# Ports.net
KiCad netlist of a schematic drawn in Altium Designer
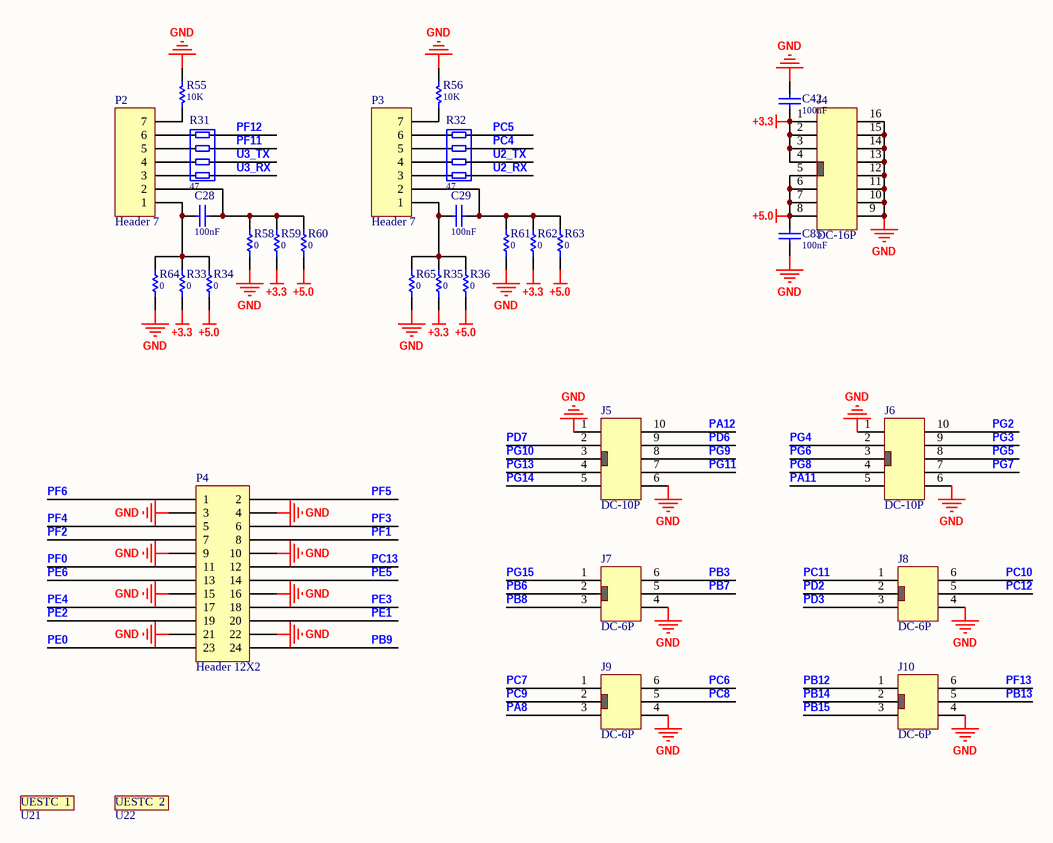
[diagram p0: Ports.SchDoc]

(export (version "E")
  (design (tool "Eeschema 10.0.6"))
  (components
    (comp (ref "C28")
      (value "100nF")
      (footprint "C0603-L")
      (description "贴片瓷片电容")
      (fields (field (name "Comment") "Cap-S"))
      (libsource (lib "xz_D") (part "Cap-S"))
    )
    (comp (ref "C29")
      (value "100nF")
      (footprint "C0603-L")
      (description "贴片瓷片电容")
      (fields (field (name "Comment") "Cap-S"))
      (libsource (lib "xz_D") (part "Cap-S"))
    )
    (comp (ref "C42")
      (value "100nF")
      (footprint "C0603-L")
      (description "贴片瓷片电容")
      (fields (field (name "Comment") "Cap-S"))
      (libsource (lib "xz_D") (part "Cap-S"))
    )
    (comp (ref "C85")
      (value "100nF")
      (footprint "C0603-L")
      (description "贴片瓷片电容")
      (fields (field (name "Comment") "Cap-S"))
      (libsource (lib "xz_D") (part "Cap-S"))
    )
    (comp (ref "J4") (value "DC-16P") (footprint "DC-16P") (libsource (lib "CommonUsed") (part "DC-16P")))
    (comp (ref "J5") (value "DC-10P") (footprint "DC-10P") (libsource (lib "CommonUsed") (part "DC-10P")))
    (comp (ref "J6") (value "DC-10P") (footprint "DC-10P") (libsource (lib "CommonUsed") (part "DC-10P")))
    (comp (ref "J7") (value "DC-6P") (footprint "DC-6P") (libsource (lib "CommonUsed") (part "DC-6P")))
    (comp (ref "J8") (value "DC-6P") (footprint "DC-6P") (libsource (lib "CommonUsed") (part "DC-6P")))
    (comp (ref "J9") (value "DC-6P") (footprint "DC-6P") (libsource (lib "CommonUsed") (part "DC-6P")))
    (comp (ref "J10") (value "DC-6P") (footprint "DC-6P") (libsource (lib "CommonUsed") (part "DC-6P")))
    (comp (ref "P2")
      (value "Header 7")
      (footprint "HDR1X7")
      (description "Header, 7-Pin")
      (fields (field (name "PUBLISHER") "Altium Limited"))
      (libsource (lib "xz_C") (part "Header 7"))
    )
    (comp (ref "P3")
      (value "Header 7")
      (footprint "HDR1X7")
      (description "Header, 7-Pin")
      (fields (field (name "PUBLISHER") "Altium Limited"))
      (libsource (lib "xz_C") (part "Header 7"))
    )
    (comp (ref "P4")
      (value "Header 12X2")
      (footprint "HDR2X12")
      (description "Header, 12-Pin, Dual row")
      (fields (field (name "PUBLISHER") "Altium Limited"))
      (libsource (lib "xz_C") (part "Header 12X2"))
    )
    (comp (ref "R31")
      (value "47")
      (footprint "R0603X4")
      (description "排阻 4")
      (fields (field (name "Comment") "R"))
      (libsource (lib "xz_D") (part "Res-4R"))
    )
    (comp (ref "R32")
      (value "47")
      (footprint "R0603X4")
      (description "排阻 4")
      (fields (field (name "Comment") "R"))
      (libsource (lib "xz_D") (part "Res-4R"))
    )
    (comp (ref "R33")
      (value "0")
      (footprint "R0603-L")
      (description "贴片电阻")
      (fields (field (name "Comment") "R"))
      (libsource (lib "xz_D") (part "Res"))
    )
    (comp (ref "R34")
      (value "0")
      (footprint "R0603-L")
      (description "贴片电阻")
      (fields (field (name "Comment") "R"))
      (libsource (lib "xz_D") (part "Res"))
    )
    (comp (ref "R35")
      (value "0")
      (footprint "R0603-L")
      (description "贴片电阻")
      (fields (field (name "Comment") "R"))
      (libsource (lib "xz_D") (part "Res"))
    )
    (comp (ref "R36")
      (value "0")
      (footprint "R0603-L")
      (description "贴片电阻")
      (fields (field (name "Comment") "R"))
      (libsource (lib "xz_D") (part "Res"))
    )
    (comp (ref "R55")
      (value "10K")
      (footprint "R0603-L")
      (description "贴片电阻")
      (fields (field (name "Comment") "R"))
      (libsource (lib "xz_D") (part "Res"))
    )
    (comp (ref "R56")
      (value "10K")
      (footprint "R0603-L")
      (description "贴片电阻")
      (fields (field (name "Comment") "R"))
      (libsource (lib "xz_D") (part "Res"))
    )
    (comp (ref "R58")
      (value "0")
      (footprint "R0603-L")
      (description "贴片电阻")
      (fields (field (name "Comment") "R"))
      (libsource (lib "xz_D") (part "Res"))
    )
    (comp (ref "R59")
      (value "0")
      (footprint "R0603-L")
      (description "贴片电阻")
      (fields (field (name "Comment") "R"))
      (libsource (lib "xz_D") (part "Res"))
    )
    (comp (ref "R60")
      (value "0")
      (footprint "R0603-L")
      (description "贴片电阻")
      (fields (field (name "Comment") "R"))
      (libsource (lib "xz_D") (part "Res"))
    )
    (comp (ref "R61")
      (value "0")
      (footprint "R0603-L")
      (description "贴片电阻")
      (fields (field (name "Comment") "R"))
      (libsource (lib "xz_D") (part "Res"))
    )
    (comp (ref "R62")
      (value "0")
      (footprint "R0603-L")
      (description "贴片电阻")
      (fields (field (name "Comment") "R"))
      (libsource (lib "xz_D") (part "Res"))
    )
    (comp (ref "R63")
      (value "0")
      (footprint "R0603-L")
      (description "贴片电阻")
      (fields (field (name "Comment") "R"))
      (libsource (lib "xz_D") (part "Res"))
    )
    (comp (ref "R64")
      (value "0")
      (footprint "R0603-L")
      (description "贴片电阻")
      (fields (field (name "Comment") "R"))
      (libsource (lib "xz_D") (part "Res"))
    )
    (comp (ref "R65")
      (value "0")
      (footprint "R0603-L")
      (description "贴片电阻")
      (fields (field (name "Comment") "R"))
      (libsource (lib "xz_D") (part "Res"))
    )
    (comp (ref "U21") (value "UESTC  1") (footprint "UESTC") (libsource (lib "CommonUsed") (part "UESTC  1")))
    (comp (ref "U22")
      (value "UESTC  2")
      (footprint "UESTC  2")
      (libsource (lib "CommonUsed") (part "UESTC  2"))
    )
  )
  (nets
    (net (code "1") (name "+3.3") (class "Default")
      (node (ref "C42") (pin "2") (pinfunction "2_2") (pintype "passive"))
      (node (ref "J4") (pin "1") (pinfunction "1_1") (pintype "passive"))
      (node (ref "J4") (pin "2") (pinfunction "2_2") (pintype "passive"))
      (node (ref "J4") (pin "3") (pinfunction "3_3") (pintype "passive"))
      (node (ref "J4") (pin "4") (pinfunction "4_4") (pintype "passive"))
      (node (ref "R33") (pin "1") (pinfunction "1_1") (pintype "passive"))
      (node (ref "R35") (pin "1") (pinfunction "1_1") (pintype "passive"))
      (node (ref "R59") (pin "1") (pinfunction "1_1") (pintype "passive"))
      (node (ref "R62") (pin "1") (pinfunction "1_1") (pintype "passive"))
    )
    (net (code "2") (name "+5.0") (class "Default")
      (node (ref "C85") (pin "1") (pinfunction "1_1") (pintype "passive"))
      (node (ref "J4") (pin "5") (pinfunction "5_5") (pintype "passive"))
      (node (ref "J4") (pin "6") (pinfunction "6_6") (pintype "passive"))
      (node (ref "J4") (pin "7") (pinfunction "7_7") (pintype "passive"))
      (node (ref "J4") (pin "8") (pinfunction "8_8") (pintype "passive"))
      (node (ref "R34") (pin "1") (pinfunction "1_1") (pintype "passive"))
      (node (ref "R36") (pin "1") (pinfunction "1_1") (pintype "passive"))
      (node (ref "R60") (pin "1") (pinfunction "1_1") (pintype "passive"))
      (node (ref "R63") (pin "1") (pinfunction "1_1") (pintype "passive"))
    )
    (net (code "3") (name "/PA8") (class "Default")
      (node (ref "J9") (pin "3") (pinfunction "3_3") (pintype "passive"))
    )
    (net (code "4") (name "/PA11") (class "Default")
      (node (ref "J6") (pin "5") (pinfunction "5_5") (pintype "passive"))
    )
    (net (code "5") (name "/PA12") (class "Default")
      (node (ref "J5") (pin "10") (pinfunction "10_10") (pintype "passive"))
    )
    (net (code "6") (name "/PB3") (class "Default")
      (node (ref "J7") (pin "6") (pinfunction "6_6") (pintype "passive"))
    )
    (net (code "7") (name "/PB6") (class "Default")
      (node (ref "J7") (pin "2") (pinfunction "2_2") (pintype "passive"))
    )
    (net (code "8") (name "/PB7") (class "Default")
      (node (ref "J7") (pin "5") (pinfunction "5_5") (pintype "passive"))
    )
    (net (code "9") (name "/PB8") (class "Default")
      (node (ref "J7") (pin "3") (pinfunction "3_3") (pintype "passive"))
    )
    (net (code "10") (name "/PB9") (class "Default")
      (node (ref "P4") (pin "24") (pinfunction "24_24") (pintype "passive"))
    )
    (net (code "11") (name "/PB12") (class "Default")
      (node (ref "J10") (pin "1") (pinfunction "1_1") (pintype "passive"))
    )
    (net (code "12") (name "/PB13") (class "Default")
      (node (ref "J10") (pin "5") (pinfunction "5_5") (pintype "passive"))
    )
    (net (code "13") (name "/PB14") (class "Default")
      (node (ref "J10") (pin "2") (pinfunction "2_2") (pintype "passive"))
    )
    (net (code "14") (name "/PB15") (class "Default")
      (node (ref "J10") (pin "3") (pinfunction "3_3") (pintype "passive"))
    )
    (net (code "15") (name "/PC4") (class "Default") (node (ref "R32") (pin "3") (pintype "passive")))
    (net (code "16") (name "/PC5") (class "Default") (node (ref "R32") (pin "4") (pintype "passive")))
    (net (code "17") (name "/PC6") (class "Default")
      (node (ref "J9") (pin "6") (pinfunction "6_6") (pintype "passive"))
    )
    (net (code "18") (name "/PC7") (class "Default")
      (node (ref "J9") (pin "1") (pinfunction "1_1") (pintype "passive"))
    )
    (net (code "19") (name "/PC8") (class "Default")
      (node (ref "J9") (pin "5") (pinfunction "5_5") (pintype "passive"))
    )
    (net (code "20") (name "/PC9") (class "Default")
      (node (ref "J9") (pin "2") (pinfunction "2_2") (pintype "passive"))
    )
    (net (code "21") (name "/PC10") (class "Default")
      (node (ref "J8") (pin "6") (pinfunction "6_6") (pintype "passive"))
    )
    (net (code "22") (name "/PC11") (class "Default")
      (node (ref "J8") (pin "1") (pinfunction "1_1") (pintype "passive"))
    )
    (net (code "23") (name "/PC12") (class "Default")
      (node (ref "J8") (pin "5") (pinfunction "5_5") (pintype "passive"))
    )
    (net (code "24") (name "/PC13") (class "Default")
      (node (ref "P4") (pin "12") (pinfunction "12_12") (pintype "passive"))
    )
    (net (code "25") (name "/PD2") (class "Default")
      (node (ref "J8") (pin "2") (pinfunction "2_2") (pintype "passive"))
    )
    (net (code "26") (name "/PD3") (class "Default")
      (node (ref "J8") (pin "3") (pinfunction "3_3") (pintype "passive"))
    )
    (net (code "27") (name "/PD6") (class "Default")
      (node (ref "J5") (pin "9") (pinfunction "9_9") (pintype "passive"))
    )
    (net (code "28") (name "/PD7") (class "Default")
      (node (ref "J5") (pin "2") (pinfunction "2_2") (pintype "passive"))
    )
    (net (code "29") (name "/PE0") (class "Default")
      (node (ref "P4") (pin "23") (pinfunction "23_23") (pintype "passive"))
    )
    (net (code "30") (name "/PE1") (class "Default")
      (node (ref "P4") (pin "20") (pinfunction "20_20") (pintype "passive"))
    )
    (net (code "31") (name "/PE2") (class "Default")
      (node (ref "P4") (pin "19") (pinfunction "19_19") (pintype "passive"))
    )
    (net (code "32") (name "/PE3") (class "Default")
      (node (ref "P4") (pin "18") (pinfunction "18_18") (pintype "passive"))
    )
    (net (code "33") (name "/PE4") (class "Default")
      (node (ref "P4") (pin "17") (pinfunction "17_17") (pintype "passive"))
    )
    (net (code "34") (name "/PE5") (class "Default")
      (node (ref "P4") (pin "14") (pinfunction "14_14") (pintype "passive"))
    )
    (net (code "35") (name "/PE6") (class "Default")
      (node (ref "P4") (pin "13") (pinfunction "13_13") (pintype "passive"))
    )
    (net (code "36") (name "/PF0") (class "Default")
      (node (ref "P4") (pin "11") (pinfunction "11_11") (pintype "passive"))
    )
    (net (code "37") (name "/PF1") (class "Default")
      (node (ref "P4") (pin "8") (pinfunction "8_8") (pintype "passive"))
    )
    (net (code "38") (name "/PF2") (class "Default")
      (node (ref "P4") (pin "7") (pinfunction "7_7") (pintype "passive"))
    )
    (net (code "39") (name "/PF3") (class "Default")
      (node (ref "P4") (pin "6") (pinfunction "6_6") (pintype "passive"))
    )
    (net (code "40") (name "/PF4") (class "Default")
      (node (ref "P4") (pin "5") (pinfunction "5_5") (pintype "passive"))
    )
    (net (code "41") (name "/PF5") (class "Default")
      (node (ref "P4") (pin "2") (pinfunction "2_2") (pintype "passive"))
    )
    (net (code "42") (name "/PF6") (class "Default")
      (node (ref "P4") (pin "1") (pinfunction "1_1") (pintype "passive"))
    )
    (net (code "43") (name "/PF11") (class "Default") (node (ref "R31") (pin "3") (pintype "passive")))
    (net (code "44") (name "/PF12") (class "Default") (node (ref "R31") (pin "4") (pintype "passive")))
    (net (code "45") (name "/PF13") (class "Default")
      (node (ref "J10") (pin "6") (pinfunction "6_6") (pintype "passive"))
    )
    (net (code "46") (name "/PG2") (class "Default")
      (node (ref "J6") (pin "10") (pinfunction "10_10") (pintype "passive"))
    )
    (net (code "47") (name "/PG3") (class "Default")
      (node (ref "J6") (pin "9") (pinfunction "9_9") (pintype "passive"))
    )
    (net (code "48") (name "/PG4") (class "Default")
      (node (ref "J6") (pin "2") (pinfunction "2_2") (pintype "passive"))
    )
    (net (code "49") (name "/PG5") (class "Default")
      (node (ref "J6") (pin "8") (pinfunction "8_8") (pintype "passive"))
    )
    (net (code "50") (name "/PG6") (class "Default")
      (node (ref "J6") (pin "3") (pinfunction "3_3") (pintype "passive"))
    )
    (net (code "51") (name "/PG7") (class "Default")
      (node (ref "J6") (pin "7") (pinfunction "7_7") (pintype "passive"))
    )
    (net (code "52") (name "/PG8") (class "Default")
      (node (ref "J6") (pin "4") (pinfunction "4_4") (pintype "passive"))
    )
    (net (code "53") (name "/PG9") (class "Default")
      (node (ref "J5") (pin "8") (pinfunction "8_8") (pintype "passive"))
    )
    (net (code "54") (name "/PG10") (class "Default")
      (node (ref "J5") (pin "3") (pinfunction "3_3") (pintype "passive"))
    )
    (net (code "55") (name "/PG11") (class "Default")
      (node (ref "J5") (pin "7") (pinfunction "7_7") (pintype "passive"))
    )
    (net (code "56") (name "/PG13") (class "Default")
      (node (ref "J5") (pin "4") (pinfunction "4_4") (pintype "passive"))
    )
    (net (code "57") (name "/PG14") (class "Default")
      (node (ref "J5") (pin "5") (pinfunction "5_5") (pintype "passive"))
    )
    (net (code "58") (name "/PG15") (class "Default")
      (node (ref "J7") (pin "1") (pinfunction "1_1") (pintype "passive"))
    )
    (net (code "59") (name "/U2_RX") (class "Default") (node (ref "R32") (pin "1") (pintype "passive")))
    (net (code "60") (name "/U2_TX") (class "Default") (node (ref "R32") (pin "2") (pintype "passive")))
    (net (code "61") (name "/U3_RX") (class "Default") (node (ref "R31") (pin "1") (pintype "passive")))
    (net (code "62") (name "/U3_TX") (class "Default") (node (ref "R31") (pin "2") (pintype "passive")))
    (net (code "63") (name "GND") (class "Default")
      (node (ref "C42") (pin "1") (pinfunction "1_1") (pintype "passive"))
      (node (ref "C85") (pin "2") (pinfunction "2_2") (pintype "passive"))
      (node (ref "J10") (pin "4") (pinfunction "4_4") (pintype "passive"))
      (node (ref "J4") (pin "10") (pinfunction "10_10") (pintype "passive"))
      (node (ref "J4") (pin "11") (pinfunction "11_11") (pintype "passive"))
      (node (ref "J4") (pin "12") (pinfunction "12_12") (pintype "passive"))
      (node (ref "J4") (pin "13") (pinfunction "13_13") (pintype "passive"))
      (node (ref "J4") (pin "14") (pinfunction "14_14") (pintype "passive"))
      (node (ref "J4") (pin "15") (pinfunction "15_15") (pintype "passive"))
      (node (ref "J4") (pin "16") (pinfunction "16_16") (pintype "passive"))
      (node (ref "J4") (pin "9") (pinfunction "9_9") (pintype "passive"))
      (node (ref "J5") (pin "1") (pinfunction "1_1") (pintype "passive"))
      (node (ref "J5") (pin "6") (pinfunction "6_6") (pintype "passive"))
      (node (ref "J6") (pin "1") (pinfunction "1_1") (pintype "passive"))
      (node (ref "J6") (pin "6") (pinfunction "6_6") (pintype "passive"))
      (node (ref "J7") (pin "4") (pinfunction "4_4") (pintype "passive"))
      (node (ref "J8") (pin "4") (pinfunction "4_4") (pintype "passive"))
      (node (ref "J9") (pin "4") (pinfunction "4_4") (pintype "passive"))
      (node (ref "P4") (pin "10") (pinfunction "10_10") (pintype "passive"))
      (node (ref "P4") (pin "15") (pinfunction "15_15") (pintype "passive"))
      (node (ref "P4") (pin "16") (pinfunction "16_16") (pintype "passive"))
      (node (ref "P4") (pin "21") (pinfunction "21_21") (pintype "passive"))
      (node (ref "P4") (pin "22") (pinfunction "22_22") (pintype "passive"))
      (node (ref "P4") (pin "3") (pinfunction "3_3") (pintype "passive"))
      (node (ref "P4") (pin "4") (pinfunction "4_4") (pintype "passive"))
      (node (ref "P4") (pin "9") (pinfunction "9_9") (pintype "passive"))
      (node (ref "R55") (pin "1") (pinfunction "1_1") (pintype "passive"))
      (node (ref "R56") (pin "1") (pinfunction "1_1") (pintype "passive"))
      (node (ref "R58") (pin "1") (pinfunction "1_1") (pintype "passive"))
      (node (ref "R61") (pin "1") (pinfunction "1_1") (pintype "passive"))
      (node (ref "R64") (pin "1") (pinfunction "1_1") (pintype "passive"))
      (node (ref "R65") (pin "1") (pinfunction "1_1") (pintype "passive"))
    )
    (net (code "64") (name "Net-(C28-Pad1)") (class "Default")
      (node (ref "C28") (pin "1") (pinfunction "1_1") (pintype "passive"))
      (node (ref "P2") (pin "2") (pinfunction "2_2") (pintype "passive"))
      (node (ref "R58") (pin "2") (pinfunction "2_2") (pintype "passive"))
      (node (ref "R59") (pin "2") (pinfunction "2_2") (pintype "passive"))
      (node (ref "R60") (pin "2") (pinfunction "2_2") (pintype "passive"))
    )
    (net (code "65") (name "Net-(C28-Pad2)") (class "Default")
      (node (ref "C28") (pin "2") (pinfunction "2_2") (pintype "passive"))
      (node (ref "P2") (pin "1") (pinfunction "1_1") (pintype "passive"))
      (node (ref "R33") (pin "2") (pinfunction "2_2") (pintype "passive"))
      (node (ref "R34") (pin "2") (pinfunction "2_2") (pintype "passive"))
      (node (ref "R64") (pin "2") (pinfunction "2_2") (pintype "passive"))
    )
    (net (code "66") (name "Net-(C29-Pad1)") (class "Default")
      (node (ref "C29") (pin "1") (pinfunction "1_1") (pintype "passive"))
      (node (ref "P3") (pin "2") (pinfunction "2_2") (pintype "passive"))
      (node (ref "R61") (pin "2") (pinfunction "2_2") (pintype "passive"))
      (node (ref "R62") (pin "2") (pinfunction "2_2") (pintype "passive"))
      (node (ref "R63") (pin "2") (pinfunction "2_2") (pintype "passive"))
    )
    (net (code "67") (name "Net-(C29-Pad2)") (class "Default")
      (node (ref "C29") (pin "2") (pinfunction "2_2") (pintype "passive"))
      (node (ref "P3") (pin "1") (pinfunction "1_1") (pintype "passive"))
      (node (ref "R35") (pin "2") (pinfunction "2_2") (pintype "passive"))
      (node (ref "R36") (pin "2") (pinfunction "2_2") (pintype "passive"))
      (node (ref "R65") (pin "2") (pinfunction "2_2") (pintype "passive"))
    )
    (net (code "68") (name "Net-(P2-Pad3)") (class "Default")
      (node (ref "P2") (pin "3") (pinfunction "3_3") (pintype "passive"))
      (node (ref "R31") (pin "8") (pintype "passive"))
    )
    (net (code "69") (name "Net-(P2-Pad4)") (class "Default")
      (node (ref "P2") (pin "4") (pinfunction "4_4") (pintype "passive"))
      (node (ref "R31") (pin "7") (pintype "passive"))
    )
    (net (code "70") (name "Net-(P2-Pad5)") (class "Default")
      (node (ref "P2") (pin "5") (pinfunction "5_5") (pintype "passive"))
      (node (ref "R31") (pin "6") (pintype "passive"))
    )
    (net (code "71") (name "Net-(P2-Pad6)") (class "Default")
      (node (ref "P2") (pin "6") (pinfunction "6_6") (pintype "passive"))
      (node (ref "R31") (pin "5") (pintype "passive"))
    )
    (net (code "72") (name "Net-(P2-Pad7)") (class "Default")
      (node (ref "P2") (pin "7") (pinfunction "7_7") (pintype "passive"))
      (node (ref "R55") (pin "2") (pinfunction "2_2") (pintype "passive"))
    )
    (net (code "73") (name "Net-(P3-Pad3)") (class "Default")
      (node (ref "P3") (pin "3") (pinfunction "3_3") (pintype "passive"))
      (node (ref "R32") (pin "8") (pintype "passive"))
    )
    (net (code "74") (name "Net-(P3-Pad4)") (class "Default")
      (node (ref "P3") (pin "4") (pinfunction "4_4") (pintype "passive"))
      (node (ref "R32") (pin "7") (pintype "passive"))
    )
    (net (code "75") (name "Net-(P3-Pad5)") (class "Default")
      (node (ref "P3") (pin "5") (pinfunction "5_5") (pintype "passive"))
      (node (ref "R32") (pin "6") (pintype "passive"))
    )
    (net (code "76") (name "Net-(P3-Pad6)") (class "Default")
      (node (ref "P3") (pin "6") (pinfunction "6_6") (pintype "passive"))
      (node (ref "R32") (pin "5") (pintype "passive"))
    )
    (net (code "77") (name "Net-(P3-Pad7)") (class "Default")
      (node (ref "P3") (pin "7") (pinfunction "7_7") (pintype "passive"))
      (node (ref "R56") (pin "2") (pinfunction "2_2") (pintype "passive"))
    )
  )
)
